# Reefing-Thermocouple.net
KiCad netlist of a schematic drawn in Altium Designer
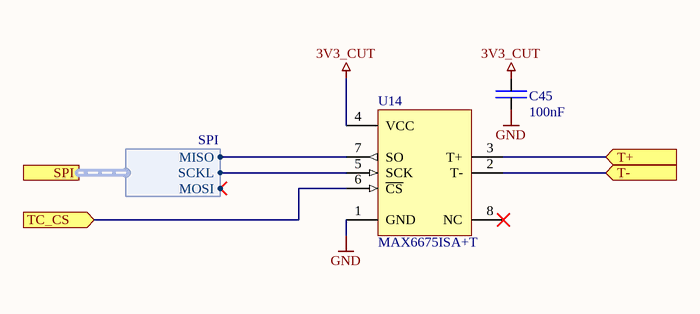
[diagram p0: Reefing-Thermocouple.SchDoc]

(export (version "E")
  (design (tool "Eeschema 10.0.6"))
  (components
    (comp (ref "C45")
      (value "100nF")
      (footprint "SMD Keramikkondensator 0402")
      (description "SMD Ceramic Capacitor E6")
      (libsource (lib "CATS-EUROC") (part "E6 - 100nF"))
    )
    (comp (ref "U14")
      (value "MAX6675ISA+T")
      (footprint "SMD IC SOIC-8")
      (description "Cold-Junction-Compensated K-Thermocoupleto-Digital Converter")
      (libsource (lib "Analog") (part "MAX6675ISA+T"))
    )
  )
  (nets
    (net (code "2") (name "/MISO") (class "Default")
      (node (ref "U14") (pin "7") (pinfunction "SO_7") (pintype "output"))
    )
    (net (code "3") (name "/SCKL") (class "Default")
      (node (ref "U14") (pin "5") (pinfunction "SCK_5") (pintype "input"))
    )
    (net (code "4") (name "/T+") (class "Default")
      (node (ref "U14") (pin "3") (pinfunction "T+_3") (pintype "passive"))
    )
    (net (code "5") (name "/T-") (class "Default")
      (node (ref "U14") (pin "2") (pinfunction "T-_2") (pintype "passive"))
    )
    (net (code "6") (name "/TC_CS") (class "Default")
      (node (ref "U14") (pin "6") (pinfunction "~{CS}_6") (pintype "input"))
    )
    (net (code "8") (name "3V3_CUT") (class "Default")
      (node (ref "C45") (pin "2") (pinfunction "2_2") (pintype "passive"))
      (node (ref "U14") (pin "4") (pinfunction "VCC_4") (pintype "passive"))
    )
    (net (code "9") (name "GND") (class "Default")
      (node (ref "C45") (pin "1") (pinfunction "1_1") (pintype "passive"))
      (node (ref "U14") (pin "1") (pinfunction "GND_1") (pintype "passive"))
    )
    (net (code "10") (name "unconnected-(U14-NC-Pad8)") (class "Default")
      (node (ref "U14") (pin "8") (pinfunction "NC_8") (pintype "passive+no_connect"))
    )
  )
)
